# EEM_Connectors.net
KiCad netlist of a schematic drawn in Altium Designer
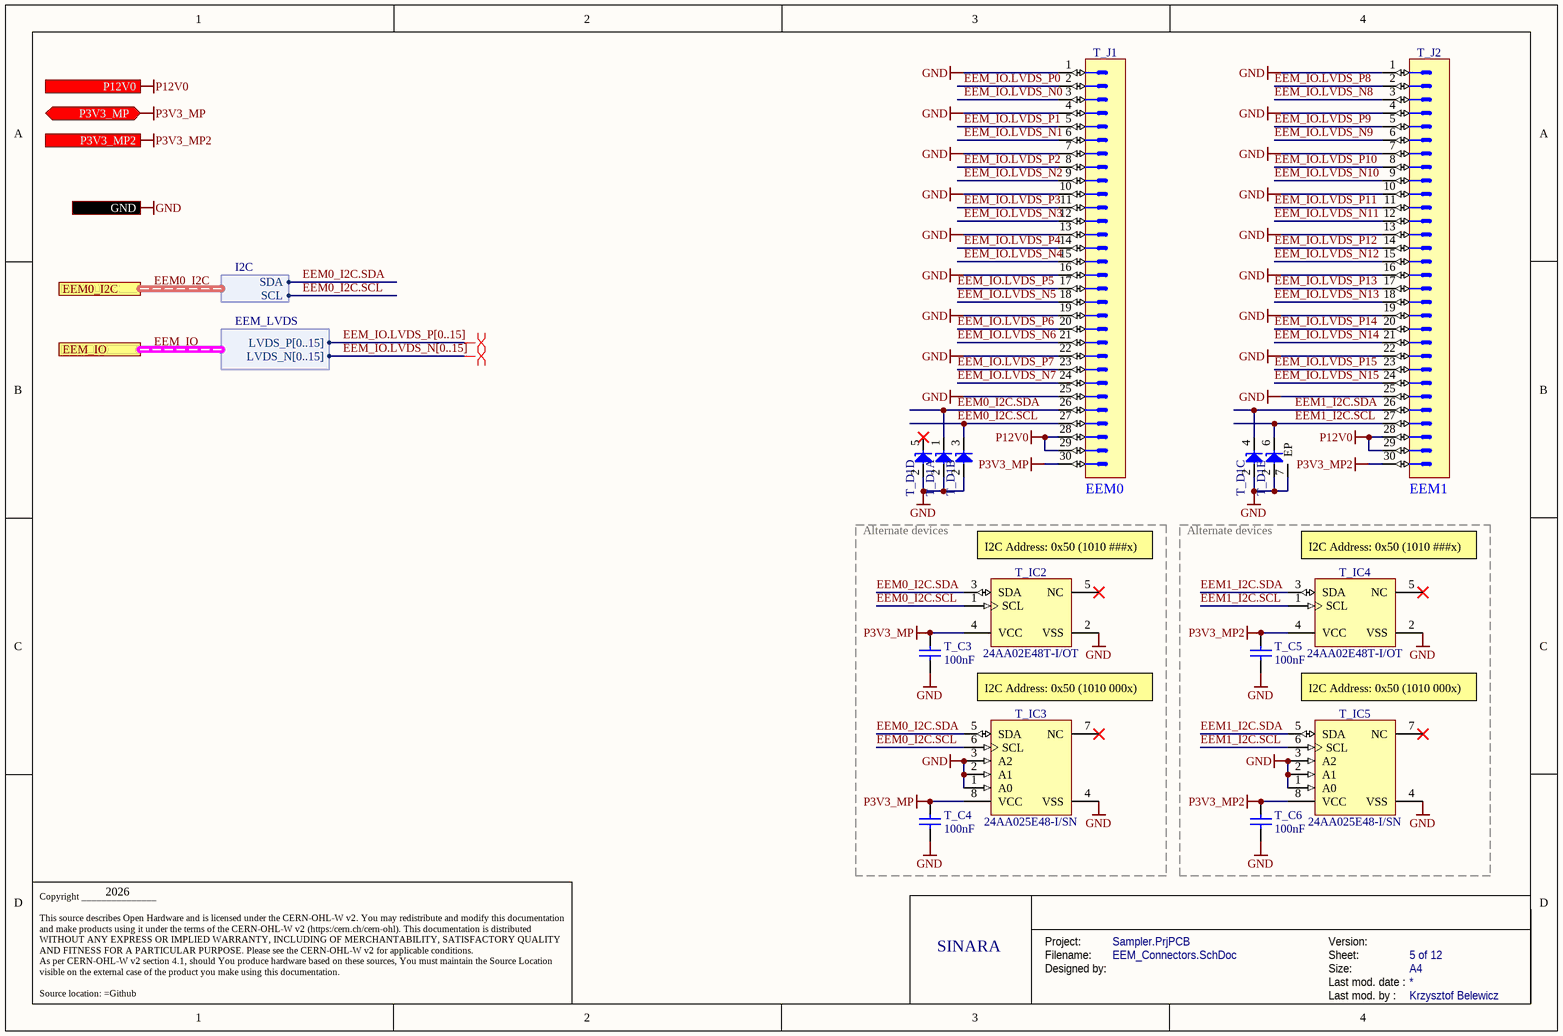
[diagram p0: EEM_Connectors.SchDoc]

(export (version "E")
  (design (tool "Eeschema 10.0.6"))
  (components
    (comp (ref "T_C3")
      (value "100nF")
      (footprint "CAPC1005X55N")
      (description "Non-polarised capacitor")
      (fields
        (field (name "PART NUMBER") "CC0402_100NF_50V_10%_X7R")
        (field (name "VOLTAGE") "50V")
        (field (name "AUTHOR") "CERN DEM MR")
      )
      (libsource (lib "Capacitors") (part "Capacitor - non polarized"))
    )
    (comp (ref "T_C4")
      (value "100nF")
      (footprint "CAPC1005X55N")
      (description "Non-polarised capacitor")
      (fields
        (field (name "PART NUMBER") "CC0402_100NF_50V_10%_X7R")
        (field (name "VOLTAGE") "50V")
        (field (name "AUTHOR") "CERN DEM MR")
      )
      (libsource (lib "Capacitors") (part "Capacitor - non polarized"))
    )
    (comp (ref "T_C5")
      (value "100nF")
      (footprint "CAPC1005X55N")
      (description "Non-polarised capacitor")
      (fields
        (field (name "PART NUMBER") "CC0402_100NF_50V_10%_X7R")
        (field (name "VOLTAGE") "50V")
        (field (name "AUTHOR") "CERN DEM MR")
      )
      (libsource (lib "Capacitors") (part "Capacitor - non polarized"))
    )
    (comp (ref "T_C6")
      (value "100nF")
      (footprint "CAPC1005X55N")
      (description "Non-polarised capacitor")
      (fields
        (field (name "PART NUMBER") "CC0402_100NF_50V_10%_X7R")
        (field (name "VOLTAGE") "50V")
        (field (name "AUTHOR") "CERN DEM MR")
      )
      (libsource (lib "Capacitors") (part "Capacitor - non polarized"))
    )
    (comp (ref "T_D1")
      (value "UCLAMP3305P.TCT")
      (footprint "SON50P160X65_HS-7N")
      (description "Diode TVS Quint Common Anode Uni-Dir 3.3V 40W 6-Pin SLP EP T/R")
      (libsource (lib "TechnoSystem Workspace") (part "D-AK-2"))
    )
    (comp (ref "T_IC2")
      (value "24AA02E48T-I/OT")
      (footprint "SOT95P280X145-5N")
      (description "1.7V-5.5V, 2K I2C Serial EEPROM With EUI-48 Node Identity")
      (fields (field (name "MANUFACTURER") "MICROCHIP TECHNOLOGY") (field (name "AUTHOR") "CERN DEM MR"))
      (libsource (lib "ICs And Semiconductors") (part "24AA02E48T-I/OT"))
    )
    (comp (ref "T_IC3")
      (value "24AA025E48-I/SN")
      (footprint "SOIC127P600X175-8N")
      (description "1.7V-5.5V, 2K I2C™ Serial EEPROMs with EUI-48™ Node Identity")
      (fields (field (name "MANUFACTURER") "MICROCHIP TECHNOLOGY") (field (name "AUTHOR") "CERN DEM MR"))
      (libsource (lib "ICs And Semiconductors") (part "24AA025E48-I/SN"))
    )
    (comp (ref "T_IC4")
      (value "24AA02E48T-I/OT")
      (footprint "SOT95P280X145-5N")
      (description "1.7V-5.5V, 2K I2C Serial EEPROM With EUI-48 Node Identity")
      (fields (field (name "MANUFACTURER") "MICROCHIP TECHNOLOGY") (field (name "AUTHOR") "CERN DEM MR"))
      (libsource (lib "ICs And Semiconductors") (part "24AA02E48T-I/OT"))
    )
    (comp (ref "T_IC5")
      (value "24AA025E48-I/SN")
      (footprint "SOIC127P600X175-8N")
      (description "1.7V-5.5V, 2K I2C™ Serial EEPROMs with EUI-48™ Node Identity")
      (fields (field (name "MANUFACTURER") "MICROCHIP TECHNOLOGY") (field (name "AUTHOR") "CERN DEM MR"))
      (libsource (lib "ICs And Semiconductors") (part "24AA025E48-I/SN"))
    )
    (comp (ref "T_J1")
      (value "~")
      (footprint "3M_N2530-6002RB")
      (description "Connector 30 Male")
      (fields
        (field (name "PART NUMBER") "3M_N2530-6002RB")
        (field (name "MANUFACTURER") "3M")
        (field (name "AUTHOR") "CERN DEM JLC")
      )
      (libsource (lib "Connectors") (part "Connector 30 Male"))
    )
    (comp (ref "T_J2")
      (value "~")
      (footprint "3M_N2530-6002RB")
      (description "Connector 30 Male")
      (fields
        (field (name "PART NUMBER") "3M_N2530-6002RB")
        (field (name "MANUFACTURER") "3M")
        (field (name "AUTHOR") "CERN DEM JLC")
      )
      (libsource (lib "Connectors") (part "Connector 30 Male"))
    )
  )
  (nets
    (net (code "3") (name "/EEM0_I2C.SCL") (class "Default")
      (node (ref "T_D1") (pin "3") (pinfunction "C_3") (pintype "passive"))
      (node (ref "T_IC2") (pin "1") (pinfunction "SCL_1") (pintype "input"))
      (node (ref "T_IC3") (pin "6") (pinfunction "SCL_6") (pintype "input"))
      (node (ref "T_J1") (pin "27") (pinfunction "27_27") (pintype "bidirectional"))
    )
    (net (code "4") (name "/EEM0_I2C.SDA") (class "Default")
      (node (ref "T_D1") (pin "1") (pinfunction "C_1") (pintype "passive"))
      (node (ref "T_IC2") (pin "3") (pinfunction "SDA_3") (pintype "bidirectional"))
      (node (ref "T_IC3") (pin "5") (pinfunction "SDA_5") (pintype "bidirectional"))
      (node (ref "T_J1") (pin "26") (pinfunction "26_26") (pintype "bidirectional"))
    )
    (net (code "6") (name "/EEM1_I2C.SCL") (class "Default")
      (node (ref "T_D1") (pin "6") (pinfunction "C_6") (pintype "passive"))
      (node (ref "T_IC4") (pin "1") (pinfunction "SCL_1") (pintype "input"))
      (node (ref "T_IC5") (pin "6") (pinfunction "SCL_6") (pintype "input"))
      (node (ref "T_J2") (pin "27") (pinfunction "27_27") (pintype "bidirectional"))
    )
    (net (code "7") (name "/EEM1_I2C.SDA") (class "Default")
      (node (ref "T_D1") (pin "4") (pinfunction "C_4") (pintype "passive"))
      (node (ref "T_IC4") (pin "3") (pinfunction "SDA_3") (pintype "bidirectional"))
      (node (ref "T_IC5") (pin "5") (pinfunction "SDA_5") (pintype "bidirectional"))
      (node (ref "T_J2") (pin "26") (pinfunction "26_26") (pintype "bidirectional"))
    )
    (net (code "8") (name "/EEM_IO.LVDS_N0") (class "Default")
      (node (ref "T_J1") (pin "3") (pinfunction "3_3") (pintype "bidirectional"))
    )
    (net (code "9") (name "/EEM_IO.LVDS_N1") (class "Default")
      (node (ref "T_J1") (pin "6") (pinfunction "6_6") (pintype "bidirectional"))
    )
    (net (code "10") (name "/EEM_IO.LVDS_N2") (class "Default")
      (node (ref "T_J1") (pin "9") (pinfunction "9_9") (pintype "bidirectional"))
    )
    (net (code "11") (name "/EEM_IO.LVDS_N3") (class "Default")
      (node (ref "T_J1") (pin "12") (pinfunction "12_12") (pintype "bidirectional"))
    )
    (net (code "12") (name "/EEM_IO.LVDS_N4") (class "Default")
      (node (ref "T_J1") (pin "15") (pinfunction "15_15") (pintype "bidirectional"))
    )
    (net (code "13") (name "/EEM_IO.LVDS_N5") (class "Default")
      (node (ref "T_J1") (pin "18") (pinfunction "18_18") (pintype "bidirectional"))
    )
    (net (code "14") (name "/EEM_IO.LVDS_N6") (class "Default")
      (node (ref "T_J1") (pin "21") (pinfunction "21_21") (pintype "bidirectional"))
    )
    (net (code "15") (name "/EEM_IO.LVDS_N7") (class "Default")
      (node (ref "T_J1") (pin "24") (pinfunction "24_24") (pintype "bidirectional"))
    )
    (net (code "16") (name "/EEM_IO.LVDS_N8") (class "Default")
      (node (ref "T_J2") (pin "3") (pinfunction "3_3") (pintype "bidirectional"))
    )
    (net (code "17") (name "/EEM_IO.LVDS_N9") (class "Default")
      (node (ref "T_J2") (pin "6") (pinfunction "6_6") (pintype "bidirectional"))
    )
    (net (code "18") (name "/EEM_IO.LVDS_N10") (class "Default")
      (node (ref "T_J2") (pin "9") (pinfunction "9_9") (pintype "bidirectional"))
    )
    (net (code "19") (name "/EEM_IO.LVDS_N11") (class "Default")
      (node (ref "T_J2") (pin "12") (pinfunction "12_12") (pintype "bidirectional"))
    )
    (net (code "20") (name "/EEM_IO.LVDS_N12") (class "Default")
      (node (ref "T_J2") (pin "15") (pinfunction "15_15") (pintype "bidirectional"))
    )
    (net (code "21") (name "/EEM_IO.LVDS_N13") (class "Default")
      (node (ref "T_J2") (pin "18") (pinfunction "18_18") (pintype "bidirectional"))
    )
    (net (code "22") (name "/EEM_IO.LVDS_N14") (class "Default")
      (node (ref "T_J2") (pin "21") (pinfunction "21_21") (pintype "bidirectional"))
    )
    (net (code "23") (name "/EEM_IO.LVDS_N15") (class "Default")
      (node (ref "T_J2") (pin "24") (pinfunction "24_24") (pintype "bidirectional"))
    )
    (net (code "24") (name "/EEM_IO.LVDS_P0") (class "Default")
      (node (ref "T_J1") (pin "2") (pinfunction "2_2") (pintype "bidirectional"))
    )
    (net (code "25") (name "/EEM_IO.LVDS_P1") (class "Default")
      (node (ref "T_J1") (pin "5") (pinfunction "5_5") (pintype "bidirectional"))
    )
    (net (code "26") (name "/EEM_IO.LVDS_P2") (class "Default")
      (node (ref "T_J1") (pin "8") (pinfunction "8_8") (pintype "bidirectional"))
    )
    (net (code "27") (name "/EEM_IO.LVDS_P3") (class "Default")
      (node (ref "T_J1") (pin "11") (pinfunction "11_11") (pintype "bidirectional"))
    )
    (net (code "28") (name "/EEM_IO.LVDS_P4") (class "Default")
      (node (ref "T_J1") (pin "14") (pinfunction "14_14") (pintype "bidirectional"))
    )
    (net (code "29") (name "/EEM_IO.LVDS_P5") (class "Default")
      (node (ref "T_J1") (pin "17") (pinfunction "17_17") (pintype "bidirectional"))
    )
    (net (code "30") (name "/EEM_IO.LVDS_P6") (class "Default")
      (node (ref "T_J1") (pin "20") (pinfunction "20_20") (pintype "bidirectional"))
    )
    (net (code "31") (name "/EEM_IO.LVDS_P7") (class "Default")
      (node (ref "T_J1") (pin "23") (pinfunction "23_23") (pintype "bidirectional"))
    )
    (net (code "32") (name "/EEM_IO.LVDS_P8") (class "Default")
      (node (ref "T_J2") (pin "2") (pinfunction "2_2") (pintype "bidirectional"))
    )
    (net (code "33") (name "/EEM_IO.LVDS_P9") (class "Default")
      (node (ref "T_J2") (pin "5") (pinfunction "5_5") (pintype "bidirectional"))
    )
    (net (code "34") (name "/EEM_IO.LVDS_P10") (class "Default")
      (node (ref "T_J2") (pin "8") (pinfunction "8_8") (pintype "bidirectional"))
    )
    (net (code "35") (name "/EEM_IO.LVDS_P11") (class "Default")
      (node (ref "T_J2") (pin "11") (pinfunction "11_11") (pintype "bidirectional"))
    )
    (net (code "36") (name "/EEM_IO.LVDS_P12") (class "Default")
      (node (ref "T_J2") (pin "14") (pinfunction "14_14") (pintype "bidirectional"))
    )
    (net (code "37") (name "/EEM_IO.LVDS_P13") (class "Default")
      (node (ref "T_J2") (pin "17") (pinfunction "17_17") (pintype "bidirectional"))
    )
    (net (code "38") (name "/EEM_IO.LVDS_P14") (class "Default")
      (node (ref "T_J2") (pin "20") (pinfunction "20_20") (pintype "bidirectional"))
    )
    (net (code "39") (name "/EEM_IO.LVDS_P15") (class "Default")
      (node (ref "T_J2") (pin "23") (pinfunction "23_23") (pintype "bidirectional"))
    )
    (net (code "42") (name "GND") (class "Default")
      (node (ref "T_C3") (pin "1") (pinfunction "1_1") (pintype "passive"))
      (node (ref "T_C4") (pin "1") (pinfunction "1_1") (pintype "passive"))
      (node (ref "T_C5") (pin "1") (pinfunction "1_1") (pintype "passive"))
      (node (ref "T_C6") (pin "1") (pinfunction "1_1") (pintype "passive"))
      (node (ref "T_D1") (pin "2") (pinfunction "A_2") (pintype "passive"))
      (node (ref "T_D1") (pin "7") (pinfunction "EP_7") (pintype "passive"))
      (node (ref "T_IC2") (pin "2") (pinfunction "VSS_2") (pintype "power_in"))
      (node (ref "T_IC3") (pin "1") (pinfunction "A0_1") (pintype "input"))
      (node (ref "T_IC3") (pin "2") (pinfunction "A1_2") (pintype "input"))
      (node (ref "T_IC3") (pin "3") (pinfunction "A2_3") (pintype "input"))
      (node (ref "T_IC3") (pin "4") (pinfunction "VSS_4") (pintype "power_in"))
      (node (ref "T_IC4") (pin "2") (pinfunction "VSS_2") (pintype "power_in"))
      (node (ref "T_IC5") (pin "1") (pinfunction "A0_1") (pintype "input"))
      (node (ref "T_IC5") (pin "2") (pinfunction "A1_2") (pintype "input"))
      (node (ref "T_IC5") (pin "3") (pinfunction "A2_3") (pintype "input"))
      (node (ref "T_IC5") (pin "4") (pinfunction "VSS_4") (pintype "power_in"))
      (node (ref "T_J1") (pin "1") (pinfunction "1_1") (pintype "bidirectional"))
      (node (ref "T_J1") (pin "10") (pinfunction "10_10") (pintype "bidirectional"))
      (node (ref "T_J1") (pin "13") (pinfunction "13_13") (pintype "bidirectional"))
      (node (ref "T_J1") (pin "16") (pinfunction "16_16") (pintype "bidirectional"))
      (node (ref "T_J1") (pin "19") (pinfunction "19_19") (pintype "bidirectional"))
      (node (ref "T_J1") (pin "22") (pinfunction "22_22") (pintype "bidirectional"))
      (node (ref "T_J1") (pin "25") (pinfunction "25_25") (pintype "bidirectional"))
      (node (ref "T_J1") (pin "4") (pinfunction "4_4") (pintype "bidirectional"))
      (node (ref "T_J1") (pin "7") (pinfunction "7_7") (pintype "bidirectional"))
      (node (ref "T_J2") (pin "1") (pinfunction "1_1") (pintype "bidirectional"))
      (node (ref "T_J2") (pin "10") (pinfunction "10_10") (pintype "bidirectional"))
      (node (ref "T_J2") (pin "13") (pinfunction "13_13") (pintype "bidirectional"))
      (node (ref "T_J2") (pin "16") (pinfunction "16_16") (pintype "bidirectional"))
      (node (ref "T_J2") (pin "19") (pinfunction "19_19") (pintype "bidirectional"))
      (node (ref "T_J2") (pin "22") (pinfunction "22_22") (pintype "bidirectional"))
      (node (ref "T_J2") (pin "25") (pinfunction "25_25") (pintype "bidirectional"))
      (node (ref "T_J2") (pin "4") (pinfunction "4_4") (pintype "bidirectional"))
      (node (ref "T_J2") (pin "7") (pinfunction "7_7") (pintype "bidirectional"))
    )
    (net (code "43") (name "P3V3_MP") (class "Default")
      (node (ref "T_C3") (pin "2") (pinfunction "2_2") (pintype "passive"))
      (node (ref "T_C4") (pin "2") (pinfunction "2_2") (pintype "passive"))
      (node (ref "T_IC2") (pin "4") (pinfunction "VCC_4") (pintype "power_in"))
      (node (ref "T_IC3") (pin "8") (pinfunction "VCC_8") (pintype "power_in"))
      (node (ref "T_J1") (pin "30") (pinfunction "30_30") (pintype "bidirectional"))
    )
    (net (code "44") (name "P3V3_MP2") (class "Default")
      (node (ref "T_C5") (pin "2") (pinfunction "2_2") (pintype "passive"))
      (node (ref "T_C6") (pin "2") (pinfunction "2_2") (pintype "passive"))
      (node (ref "T_IC4") (pin "4") (pinfunction "VCC_4") (pintype "power_in"))
      (node (ref "T_IC5") (pin "8") (pinfunction "VCC_8") (pintype "power_in"))
      (node (ref "T_J2") (pin "30") (pinfunction "30_30") (pintype "bidirectional"))
    )
    (net (code "45") (name "P12V0") (class "Default")
      (node (ref "T_J1") (pin "28") (pinfunction "28_28") (pintype "bidirectional"))
      (node (ref "T_J1") (pin "29") (pinfunction "29_29") (pintype "bidirectional"))
      (node (ref "T_J2") (pin "28") (pinfunction "28_28") (pintype "bidirectional"))
      (node (ref "T_J2") (pin "29") (pinfunction "29_29") (pintype "bidirectional"))
    )
    (net (code "46") (name "unconnected-(T_D1D-C-Pad5)") (class "Default")
      (node (ref "T_D1") (pin "5") (pinfunction "C_5") (pintype "passive+no_connect"))
    )
    (net (code "47") (name "unconnected-(T_IC2-NC-Pad5)") (class "Default")
      (node (ref "T_IC2") (pin "5") (pinfunction "NC_5") (pintype "passive+no_connect"))
    )
    (net (code "48") (name "unconnected-(T_IC3-NC-Pad7)") (class "Default")
      (node (ref "T_IC3") (pin "7") (pinfunction "NC_7") (pintype "passive+no_connect"))
    )
    (net (code "49") (name "unconnected-(T_IC4-NC-Pad5)") (class "Default")
      (node (ref "T_IC4") (pin "5") (pinfunction "NC_5") (pintype "passive+no_connect"))
    )
    (net (code "50") (name "unconnected-(T_IC5-NC-Pad7)") (class "Default")
      (node (ref "T_IC5") (pin "7") (pinfunction "NC_7") (pintype "passive+no_connect"))
    )
  )
)
